# exchange_pcb.net
KiCad netlist of a schematic drawn in Altium Designer
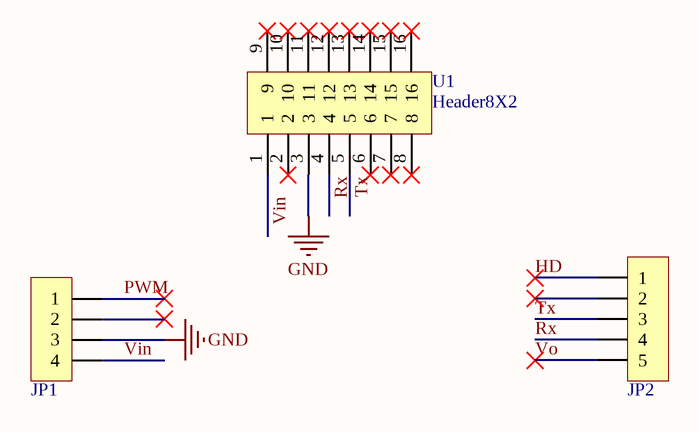
[diagram p0: exchange_pcb.SchDoc]

(export (version "E")
  (design (tool "Eeschema 10.0.6"))
  (components
    (comp (ref "JP1")
      (value "HDR-1X4")
      (footprint "HDR2.54-M-LI-4P")
      (description "4P接插件")
      (fields (field (name "版权归属") "封装库来自淘宝 ID：黄晶宝石"))
      (libsource (lib "5.4 - 接插件-脚距2.54 (100mil) ") (part "Header 4"))
    )
    (comp (ref "JP2")
      (value "HDR-1X5")
      (footprint "HDR2.54-M-LI-5P")
      (description "5P接插件")
      (fields (field (name "版权归属") "封装库来自淘宝 ID：黄晶宝石"))
      (libsource (lib "5.4 - 接插件-脚距2.54 (100mil) ") (part "Header 5"))
    )
    (comp (ref "U1") (value "Header8X2") (footprint "header8X2") (libsource (lib "主控1.1") (part "Header8X2")))
  )
  (nets
    (net (code "1") (name "/HD") (class "Default")
      (node (ref "JP2") (pin "1") (pinfunction "1_1") (pintype "passive+no_connect"))
    )
    (net (code "2") (name "/PWM") (class "Default")
      (node (ref "JP1") (pin "1") (pinfunction "1_1") (pintype "passive+no_connect"))
    )
    (net (code "3") (name "/Rx") (class "Default")
      (node (ref "JP2") (pin "4") (pinfunction "4_4") (pintype "passive"))
      (node (ref "U1") (pin "4") (pinfunction "4_4") (pintype "passive"))
    )
    (net (code "4") (name "/Tx") (class "Default")
      (node (ref "JP2") (pin "3") (pinfunction "3_3") (pintype "passive"))
      (node (ref "U1") (pin "5") (pinfunction "5_5") (pintype "passive"))
    )
    (net (code "5") (name "/Vin") (class "Default")
      (node (ref "JP1") (pin "4") (pinfunction "4_4") (pintype "passive"))
      (node (ref "U1") (pin "1") (pinfunction "1_1") (pintype "passive"))
    )
    (net (code "6") (name "/Vo") (class "Default")
      (node (ref "JP2") (pin "5") (pinfunction "5_5") (pintype "passive+no_connect"))
    )
    (net (code "7") (name "GND") (class "Default")
      (node (ref "JP1") (pin "3") (pinfunction "3_3") (pintype "passive"))
      (node (ref "U1") (pin "3") (pinfunction "3_3") (pintype "passive"))
    )
    (net (code "8") (name "unconnected-(JP1-Pad2)") (class "Default")
      (node (ref "JP1") (pin "2") (pinfunction "2_2") (pintype "passive+no_connect"))
    )
    (net (code "9") (name "unconnected-(JP2-Pad2)") (class "Default")
      (node (ref "JP2") (pin "2") (pinfunction "2_2") (pintype "passive+no_connect"))
    )
    (net (code "10") (name "unconnected-(U1-Pad2)") (class "Default")
      (node (ref "U1") (pin "2") (pinfunction "2_2") (pintype "passive+no_connect"))
    )
    (net (code "11") (name "unconnected-(U1-Pad6)") (class "Default")
      (node (ref "U1") (pin "6") (pinfunction "6_6") (pintype "passive+no_connect"))
    )
    (net (code "12") (name "unconnected-(U1-Pad7)") (class "Default")
      (node (ref "U1") (pin "7") (pinfunction "7_7") (pintype "passive+no_connect"))
    )
    (net (code "13") (name "unconnected-(U1-Pad8)") (class "Default")
      (node (ref "U1") (pin "8") (pinfunction "8_8") (pintype "passive+no_connect"))
    )
    (net (code "14") (name "unconnected-(U1-Pad9)") (class "Default")
      (node (ref "U1") (pin "9") (pinfunction "9_9") (pintype "passive+no_connect"))
    )
    (net (code "15") (name "unconnected-(U1-Pad10)") (class "Default")
      (node (ref "U1") (pin "10") (pinfunction "10_10") (pintype "passive+no_connect"))
    )
    (net (code "16") (name "unconnected-(U1-Pad11)") (class "Default")
      (node (ref "U1") (pin "11") (pinfunction "11_11") (pintype "passive+no_connect"))
    )
    (net (code "17") (name "unconnected-(U1-Pad12)") (class "Default")
      (node (ref "U1") (pin "12") (pinfunction "12_12") (pintype "passive+no_connect"))
    )
    (net (code "18") (name "unconnected-(U1-Pad13)") (class "Default")
      (node (ref "U1") (pin "13") (pinfunction "13_13") (pintype "passive+no_connect"))
    )
    (net (code "19") (name "unconnected-(U1-Pad14)") (class "Default")
      (node (ref "U1") (pin "14") (pinfunction "14_14") (pintype "passive+no_connect"))
    )
    (net (code "20") (name "unconnected-(U1-Pad15)") (class "Default")
      (node (ref "U1") (pin "15") (pinfunction "15_15") (pintype "passive+no_connect"))
    )
    (net (code "21") (name "unconnected-(U1-Pad16)") (class "Default")
      (node (ref "U1") (pin "16") (pinfunction "16_16") (pintype "passive+no_connect"))
    )
  )
)
